# SCH_Basic_ESC_2023-04-21_EasyEDA.net
KiCad netlist of a schematic drawn in EasyEDA
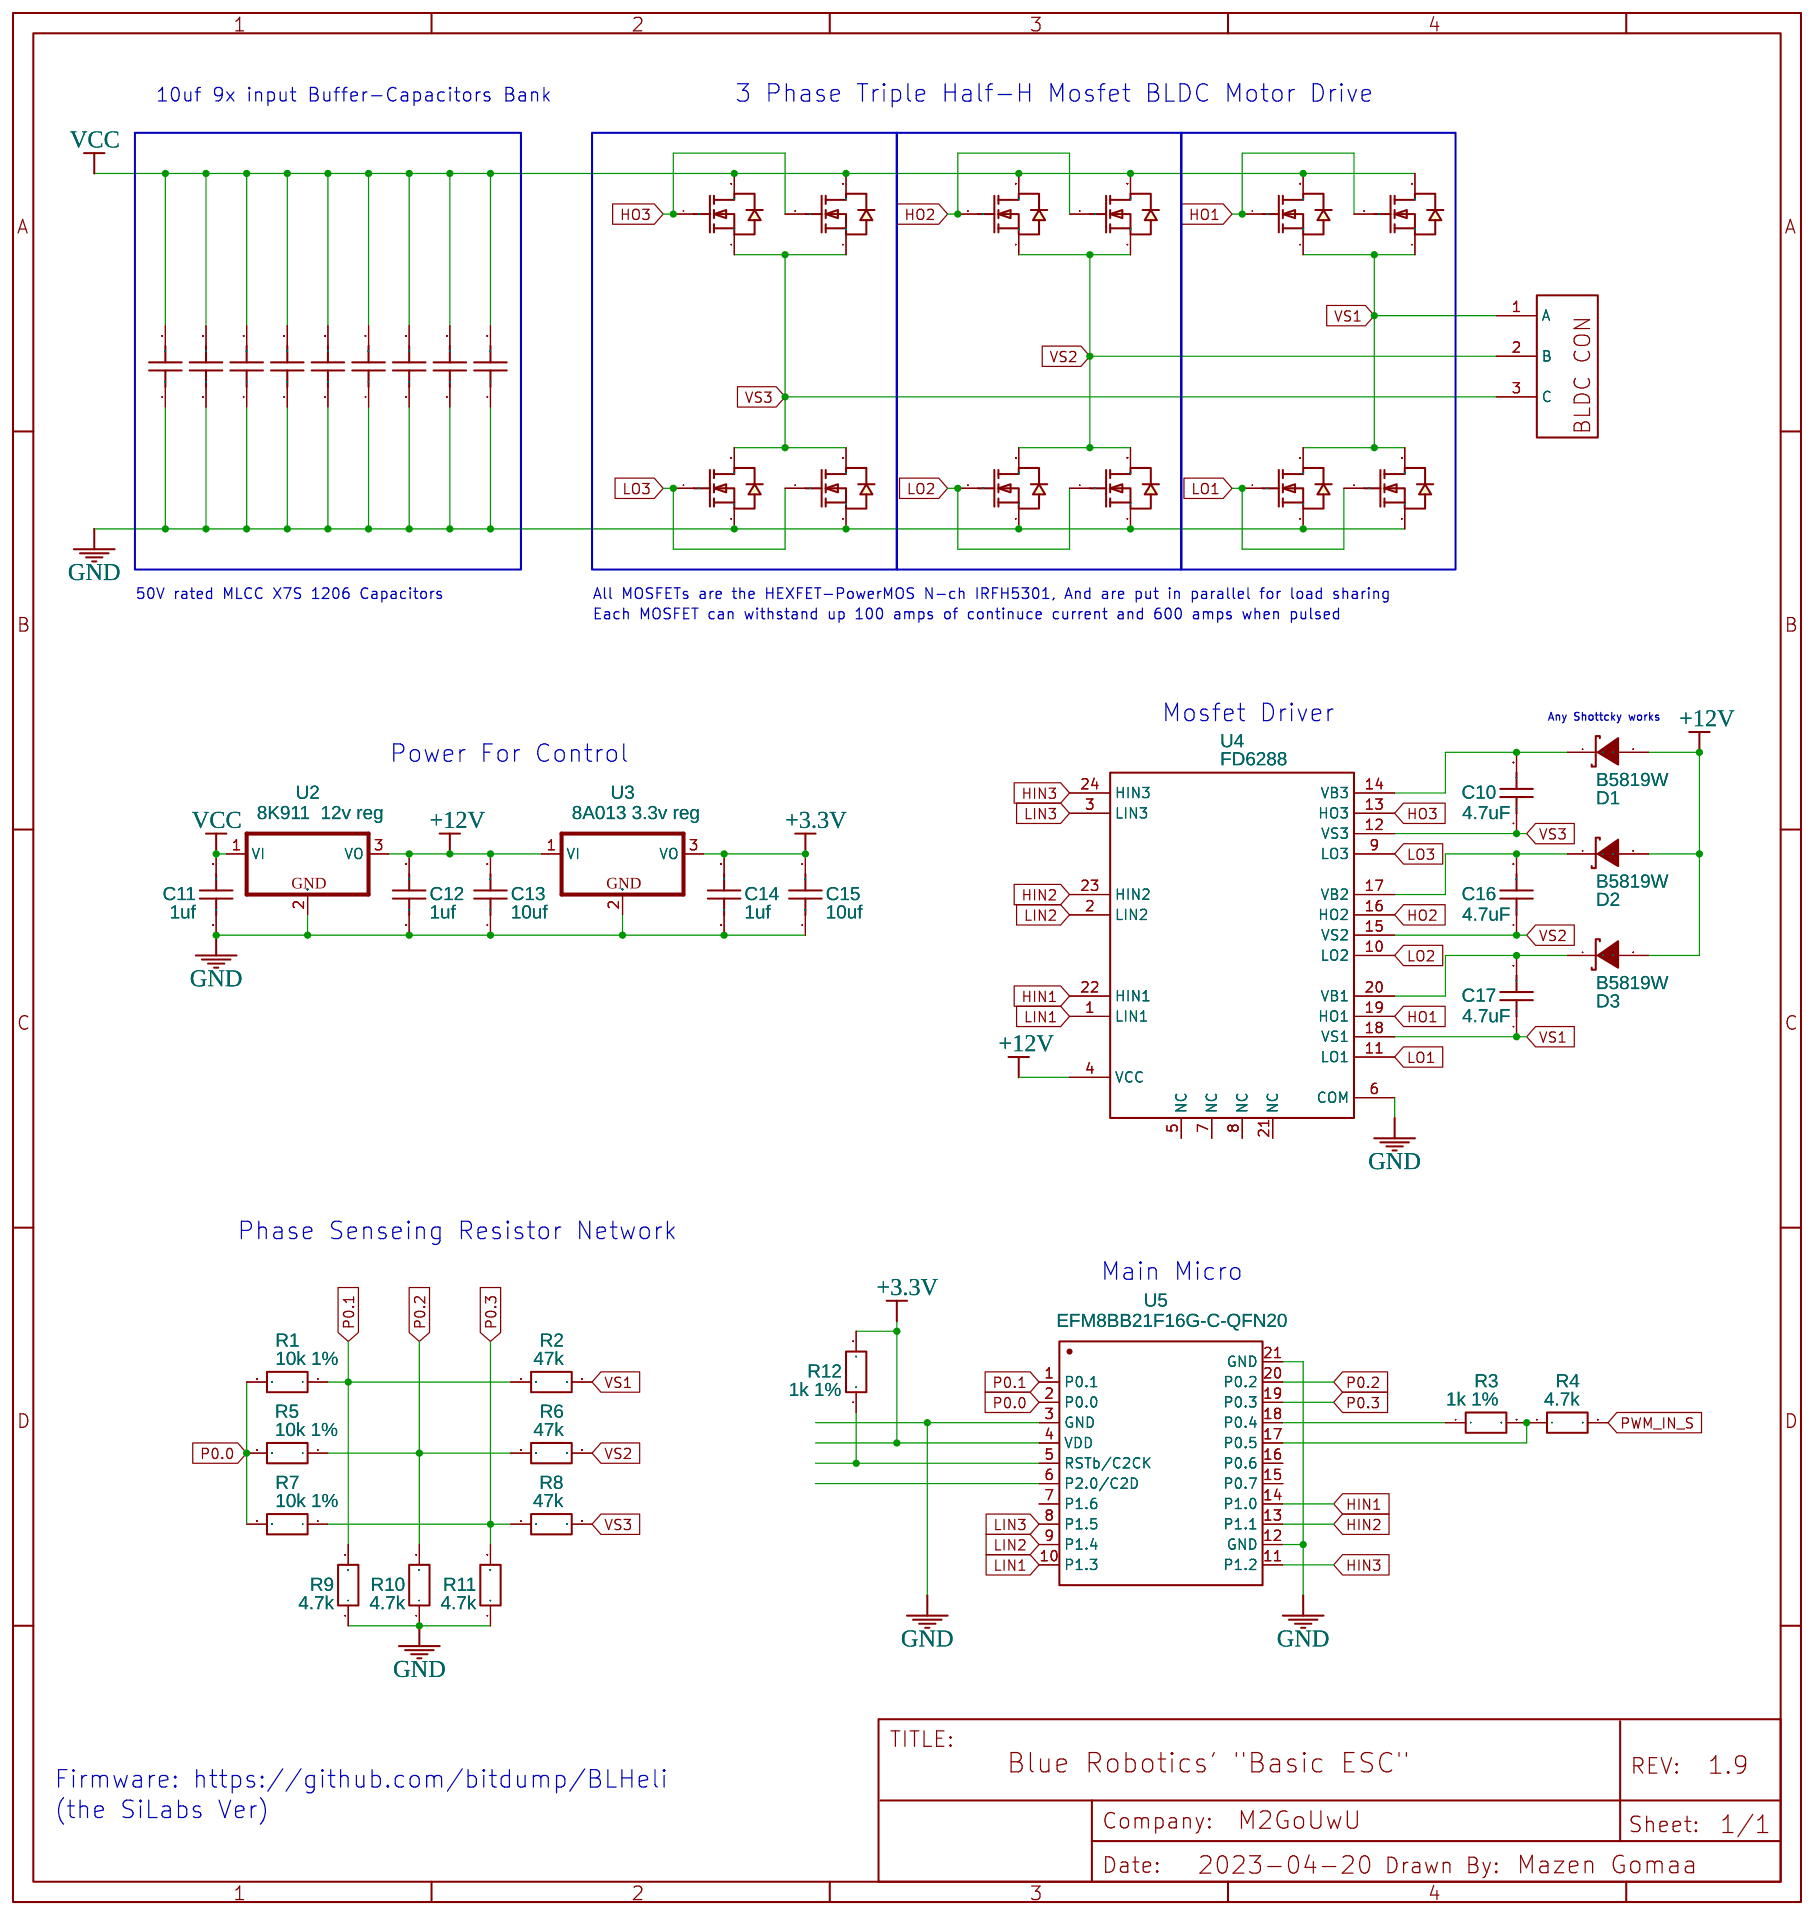
[diagram p0: schematic sheet]

(export (version "E")
  (design (tool "Eeschema 10.0.6"))
  (components
    (comp (ref "C1") (value "10uf") (libsource (lib "") (part "C_0603_US")))
    (comp (ref "C2") (value "10uf") (libsource (lib "") (part "C_0603_US")))
    (comp (ref "C3") (value "10uf") (libsource (lib "") (part "C_0603_US")))
    (comp (ref "C4") (value "10uf") (libsource (lib "") (part "C_0603_US")))
    (comp (ref "C5") (value "10uf") (libsource (lib "") (part "C_0603_US")))
    (comp (ref "C6") (value "10uf") (libsource (lib "") (part "C_0603_US")))
    (comp (ref "C7") (value "10uf") (libsource (lib "") (part "C_0603_US")))
    (comp (ref "C8") (value "10uf") (libsource (lib "") (part "C_0603_US")))
    (comp (ref "C9") (value "10uf") (libsource (lib "") (part "C_0603_US")))
    (comp (ref "C10")
      (value "4.7uF")
      (fields
        (field (name "BOM_Manufacturer Part") "TCC1206X5R475K160HT")
        (field (name "BOM_Supplier Part") "C380360")
      )
      (libsource (lib "") (part "TCC1206X5R475K160HT"))
    )
    (comp (ref "C11") (value "1uf") (libsource (lib "") (part "C_0603_US_1")))
    (comp (ref "C12") (value "1uf") (libsource (lib "") (part "C_0603_US")))
    (comp (ref "C13") (value "10uf") (libsource (lib "") (part "C_0603_US")))
    (comp (ref "C14") (value "1uf") (libsource (lib "") (part "C_0603_US")))
    (comp (ref "C15") (value "10uf") (libsource (lib "") (part "C_0603_US")))
    (comp (ref "C16")
      (value "4.7uF")
      (fields
        (field (name "BOM_Manufacturer Part") "TCC1206X5R475K160HT")
        (field (name "BOM_Supplier Part") "C380360")
      )
      (libsource (lib "") (part "TCC1206X5R475K160HT"))
    )
    (comp (ref "C17")
      (value "4.7uF")
      (fields
        (field (name "BOM_Manufacturer Part") "TCC1206X5R475K160HT")
        (field (name "BOM_Supplier Part") "C380360")
      )
      (libsource (lib "") (part "TCC1206X5R475K160HT"))
    )
    (comp (ref "D1")
      (value "B5819W")
      (fields (field (name "BOM_Supplier Part") "C64885"))
      (libsource (lib "") (part "B5819W"))
    )
    (comp (ref "D2")
      (value "B5819W")
      (fields (field (name "BOM_Supplier Part") "C64885"))
      (libsource (lib "") (part "B5819W"))
    )
    (comp (ref "D3")
      (value "B5819W")
      (fields (field (name "BOM_Supplier Part") "C64885"))
      (libsource (lib "") (part "B5819W"))
    )
    (comp (ref "Q1")
      (value "IRFH5301")
      (fields
        (field (name "BOM_Manufacturer Part") "IRFH5301PbF")
        (field (name "BOM_Supplier Part") "C82057")
      )
      (libsource (lib "") (part "IRFH5301"))
    )
    (comp (ref "Q2")
      (value "IRFH5301")
      (fields
        (field (name "BOM_Manufacturer Part") "IRFH5301PbF")
        (field (name "BOM_Supplier Part") "C82057")
      )
      (libsource (lib "") (part "IRFH5301"))
    )
    (comp (ref "Q3")
      (value "IRFH5301")
      (fields
        (field (name "BOM_Manufacturer Part") "IRFH5301PbF")
        (field (name "BOM_Supplier Part") "C82057")
      )
      (libsource (lib "") (part "IRFH5301"))
    )
    (comp (ref "Q4")
      (value "IRFH5301")
      (fields
        (field (name "BOM_Manufacturer Part") "IRFH5301PbF")
        (field (name "BOM_Supplier Part") "C82057")
      )
      (libsource (lib "") (part "IRFH5301"))
    )
    (comp (ref "Q5")
      (value "IRFH5301")
      (fields
        (field (name "BOM_Manufacturer Part") "IRFH5301PbF")
        (field (name "BOM_Supplier Part") "C82057")
      )
      (libsource (lib "") (part "IRFH5301"))
    )
    (comp (ref "Q6")
      (value "IRFH5301")
      (fields
        (field (name "BOM_Manufacturer Part") "IRFH5301PbF")
        (field (name "BOM_Supplier Part") "C82057")
      )
      (libsource (lib "") (part "IRFH5301"))
    )
    (comp (ref "Q7")
      (value "IRFH5301")
      (fields
        (field (name "BOM_Manufacturer Part") "IRFH5301PbF")
        (field (name "BOM_Supplier Part") "C82057")
      )
      (libsource (lib "") (part "IRFH5301"))
    )
    (comp (ref "Q8")
      (value "IRFH5301")
      (fields
        (field (name "BOM_Manufacturer Part") "IRFH5301PbF")
        (field (name "BOM_Supplier Part") "C82057")
      )
      (libsource (lib "") (part "IRFH5301"))
    )
    (comp (ref "Q9")
      (value "IRFH5301")
      (fields
        (field (name "BOM_Manufacturer Part") "IRFH5301PbF")
        (field (name "BOM_Supplier Part") "C82057")
      )
      (libsource (lib "") (part "IRFH5301"))
    )
    (comp (ref "Q10")
      (value "IRFH5301")
      (fields
        (field (name "BOM_Manufacturer Part") "IRFH5301PbF")
        (field (name "BOM_Supplier Part") "C82057")
      )
      (libsource (lib "") (part "IRFH5301"))
    )
    (comp (ref "Q11")
      (value "IRFH5301")
      (fields
        (field (name "BOM_Manufacturer Part") "IRFH5301PbF")
        (field (name "BOM_Supplier Part") "C82057")
      )
      (libsource (lib "") (part "IRFH5301"))
    )
    (comp (ref "Q12")
      (value "IRFH5301")
      (fields
        (field (name "BOM_Manufacturer Part") "IRFH5301PbF")
        (field (name "BOM_Supplier Part") "C82057")
      )
      (libsource (lib "") (part "IRFH5301"))
    )
    (comp (ref "R1") (value "10k 1%") (libsource (lib "") (part "R_0603_EU_2")))
    (comp (ref "R2") (value "47k") (libsource (lib "") (part "R_0603_EU_1")))
    (comp (ref "R3") (value "1k 1%") (libsource (lib "") (part "R_0603_EU_1")))
    (comp (ref "R4") (value "4.7k") (libsource (lib "") (part "R_0603_EU_1")))
    (comp (ref "R5") (value "10k 1%") (libsource (lib "") (part "R_0603_EU_2")))
    (comp (ref "R6") (value "47k") (libsource (lib "") (part "R_0603_EU_1")))
    (comp (ref "R7") (value "10k 1%") (libsource (lib "") (part "R_0603_EU_2")))
    (comp (ref "R8") (value "47k") (libsource (lib "") (part "R_0603_EU_1")))
    (comp (ref "R9") (value "4.7k") (libsource (lib "") (part "R_0603_EU")))
    (comp (ref "R10") (value "4.7k") (libsource (lib "") (part "R_0603_EU")))
    (comp (ref "R11") (value "4.7k") (libsource (lib "") (part "R_0603_EU")))
    (comp (ref "R12") (value "1k 1%") (libsource (lib "") (part "R_0603_EU")))
    (comp (ref "U1") (value "BLDC_CON") (libsource (lib "") (part "BLDC_CON")))
    (comp (ref "U2")
      (value "8K911  12v reg")
      (fields
        (field (name "BOM_Manufacturer Part") "K7805-2000L")
        (field (name "BOM_Supplier Part") "C96398")
      )
      (libsource (lib "") (part "K7805-2000L"))
    )
    (comp (ref "U3")
      (value "8A013 3.3v reg")
      (fields
        (field (name "BOM_Manufacturer Part") "K7805-2000L")
        (field (name "BOM_Supplier Part") "C96398")
      )
      (libsource (lib "") (part "K7805-2000L"))
    )
    (comp (ref "U4")
      (value "FD6288")
      (fields (field (name "BOM_Manufacturer Part") "FD6288T") (field (name "BOM_Supplier Part") "C97683"))
      (libsource (lib "") (part "FD6288"))
    )
    (comp (ref "U5")
      (value "EFM8BB21F16G-C-QFN20")
      (fields
        (field (name "BOM_Manufacturer Part") "EFM8BB21F16A-C-QFN20")
        (field (name "BOM_Supplier Part") "C430129")
      )
      (libsource (lib "") (part "EFM8BB21F16A-C-QFN20"))
    )
  )
  (nets
    (net (code "1") (name "+3.3V") (class "Default")
      (node (ref "C14") (pin "2") (pinfunction "2_2") (pintype "unspecified"))
      (node (ref "C15") (pin "2") (pinfunction "2_2") (pintype "unspecified"))
      (node (ref "R12") (pin "2") (pinfunction "2_2") (pintype "unspecified"))
      (node (ref "U3") (pin "3") (pinfunction "VO_3") (pintype "unspecified"))
      (node (ref "U5") (pin "4") (pinfunction "VDD_4") (pintype "unspecified"))
    )
    (net (code "2") (name "+12V") (class "Default")
      (node (ref "C12") (pin "2") (pinfunction "2_2") (pintype "unspecified"))
      (node (ref "C13") (pin "2") (pinfunction "2_2") (pintype "unspecified"))
      (node (ref "D1") (pin "2") (pinfunction "A_2") (pintype "unspecified"))
      (node (ref "D2") (pin "2") (pinfunction "A_2") (pintype "unspecified"))
      (node (ref "D3") (pin "2") (pinfunction "A_2") (pintype "unspecified"))
      (node (ref "U2") (pin "3") (pinfunction "VO_3") (pintype "unspecified"))
      (node (ref "U3") (pin "1") (pinfunction "VI_1") (pintype "input"))
      (node (ref "U4") (pin "4") (pinfunction "VCC_4") (pintype "unspecified"))
    )
    (net (code "3") (name "GND") (class "Default")
      (node (ref "C1") (pin "1") (pinfunction "1_1") (pintype "unspecified"))
      (node (ref "C11") (pin "1") (pinfunction "1_1") (pintype "unspecified"))
      (node (ref "C12") (pin "1") (pinfunction "1_1") (pintype "unspecified"))
      (node (ref "C13") (pin "1") (pinfunction "1_1") (pintype "unspecified"))
      (node (ref "C14") (pin "1") (pinfunction "1_1") (pintype "unspecified"))
      (node (ref "C15") (pin "1") (pinfunction "1_1") (pintype "unspecified"))
      (node (ref "C2") (pin "1") (pinfunction "1_1") (pintype "unspecified"))
      (node (ref "C3") (pin "1") (pinfunction "1_1") (pintype "unspecified"))
      (node (ref "C4") (pin "1") (pinfunction "1_1") (pintype "unspecified"))
      (node (ref "C5") (pin "1") (pinfunction "1_1") (pintype "unspecified"))
      (node (ref "C6") (pin "1") (pinfunction "1_1") (pintype "unspecified"))
      (node (ref "C7") (pin "1") (pinfunction "1_1") (pintype "unspecified"))
      (node (ref "C8") (pin "1") (pinfunction "1_1") (pintype "unspecified"))
      (node (ref "C9") (pin "1") (pinfunction "1_1") (pintype "unspecified"))
      (node (ref "Q10") (pin "1") (pinfunction "S_1") (pintype "unspecified"))
      (node (ref "Q11") (pin "1") (pinfunction "S_1") (pintype "unspecified"))
      (node (ref "Q12") (pin "1") (pinfunction "S_1") (pintype "unspecified"))
      (node (ref "Q7") (pin "1") (pinfunction "S_1") (pintype "unspecified"))
      (node (ref "Q8") (pin "1") (pinfunction "S_1") (pintype "unspecified"))
      (node (ref "Q9") (pin "1") (pinfunction "S_1") (pintype "unspecified"))
      (node (ref "R10") (pin "1") (pinfunction "1_1") (pintype "unspecified"))
      (node (ref "R11") (pin "1") (pinfunction "1_1") (pintype "unspecified"))
      (node (ref "R9") (pin "1") (pinfunction "1_1") (pintype "unspecified"))
      (node (ref "U2") (pin "2") (pinfunction "GND_2") (pintype "unspecified"))
      (node (ref "U3") (pin "2") (pinfunction "GND_2") (pintype "unspecified"))
      (node (ref "U4") (pin "6") (pinfunction "COM_6") (pintype "unspecified"))
      (node (ref "U5") (pin "12") (pinfunction "GND_12") (pintype "unspecified"))
      (node (ref "U5") (pin "21") (pinfunction "GND_21") (pintype "unspecified"))
      (node (ref "U5") (pin "3") (pinfunction "GND_3") (pintype "unspecified"))
    )
    (net (code "4") (name "HIN1") (class "Default")
      (node (ref "U4") (pin "22") (pinfunction "HIN1_22") (pintype "unspecified"))
      (node (ref "U5") (pin "14") (pinfunction "P1.0_14") (pintype "unspecified"))
    )
    (net (code "5") (name "HIN2") (class "Default")
      (node (ref "U4") (pin "23") (pinfunction "HIN2_23") (pintype "unspecified"))
      (node (ref "U5") (pin "13") (pinfunction "P1.1_13") (pintype "unspecified"))
    )
    (net (code "6") (name "HIN3") (class "Default")
      (node (ref "U4") (pin "24") (pinfunction "HIN3_24") (pintype "unspecified"))
      (node (ref "U5") (pin "11") (pinfunction "P1.2_11") (pintype "unspecified"))
    )
    (net (code "7") (name "HO1") (class "Default")
      (node (ref "Q5") (pin "4") (pinfunction "G_4") (pintype "unspecified"))
      (node (ref "Q6") (pin "4") (pinfunction "G_4") (pintype "unspecified"))
      (node (ref "U4") (pin "19") (pinfunction "HO1_19") (pintype "unspecified"))
    )
    (net (code "8") (name "HO2") (class "Default")
      (node (ref "Q3") (pin "4") (pinfunction "G_4") (pintype "unspecified"))
      (node (ref "Q4") (pin "4") (pinfunction "G_4") (pintype "unspecified"))
      (node (ref "U4") (pin "16") (pinfunction "HO2_16") (pintype "unspecified"))
    )
    (net (code "9") (name "HO3") (class "Default")
      (node (ref "Q1") (pin "4") (pinfunction "G_4") (pintype "unspecified"))
      (node (ref "Q2") (pin "4") (pinfunction "G_4") (pintype "unspecified"))
      (node (ref "U4") (pin "13") (pinfunction "HO3_13") (pintype "unspecified"))
    )
    (net (code "10") (name "LIN1") (class "Default")
      (node (ref "U4") (pin "1") (pinfunction "LIN1_1") (pintype "unspecified"))
      (node (ref "U5") (pin "10") (pinfunction "P1.3_10") (pintype "unspecified"))
    )
    (net (code "11") (name "LIN2") (class "Default")
      (node (ref "U4") (pin "2") (pinfunction "LIN2_2") (pintype "unspecified"))
      (node (ref "U5") (pin "9") (pinfunction "P1.4_9") (pintype "unspecified"))
    )
    (net (code "12") (name "LIN3") (class "Default")
      (node (ref "U4") (pin "3") (pinfunction "LIN3_3") (pintype "unspecified"))
      (node (ref "U5") (pin "8") (pinfunction "P1.5_8") (pintype "unspecified"))
    )
    (net (code "13") (name "LO1") (class "Default")
      (node (ref "Q11") (pin "4") (pinfunction "G_4") (pintype "unspecified"))
      (node (ref "Q12") (pin "4") (pinfunction "G_4") (pintype "unspecified"))
      (node (ref "U4") (pin "11") (pinfunction "LO1_11") (pintype "unspecified"))
    )
    (net (code "14") (name "LO2") (class "Default")
      (node (ref "Q10") (pin "4") (pinfunction "G_4") (pintype "unspecified"))
      (node (ref "Q9") (pin "4") (pinfunction "G_4") (pintype "unspecified"))
      (node (ref "U4") (pin "10") (pinfunction "LO2_10") (pintype "unspecified"))
    )
    (net (code "15") (name "LO3") (class "Default")
      (node (ref "Q7") (pin "4") (pinfunction "G_4") (pintype "unspecified"))
      (node (ref "Q8") (pin "4") (pinfunction "G_4") (pintype "unspecified"))
      (node (ref "U4") (pin "9") (pinfunction "LO3_9") (pintype "unspecified"))
    )
    (net (code "16") (name "Net-(D1-K)") (class "Default")
      (node (ref "C10") (pin "2") (pinfunction "2_2") (pintype "unspecified"))
      (node (ref "D1") (pin "1") (pinfunction "K_1") (pintype "unspecified"))
      (node (ref "U4") (pin "14") (pinfunction "VB3_14") (pintype "unspecified"))
    )
    (net (code "17") (name "Net-(D2-K)") (class "Default")
      (node (ref "C16") (pin "2") (pinfunction "2_2") (pintype "unspecified"))
      (node (ref "D2") (pin "1") (pinfunction "K_1") (pintype "unspecified"))
      (node (ref "U4") (pin "17") (pinfunction "VB2_17") (pintype "unspecified"))
    )
    (net (code "18") (name "Net-(D3-K)") (class "Default")
      (node (ref "C17") (pin "2") (pinfunction "2_2") (pintype "unspecified"))
      (node (ref "D3") (pin "1") (pinfunction "K_1") (pintype "unspecified"))
      (node (ref "U4") (pin "20") (pinfunction "VB1_20") (pintype "unspecified"))
    )
    (net (code "19") (name "Net-(U5-P0.4)") (class "Default")
      (node (ref "R3") (pin "1") (pinfunction "1_1") (pintype "unspecified"))
      (node (ref "U5") (pin "18") (pinfunction "P0.4_18") (pintype "unspecified"))
    )
    (net (code "20") (name "Net-(U5-P0.5)") (class "Default")
      (node (ref "R3") (pin "2") (pinfunction "2_2") (pintype "unspecified"))
      (node (ref "R4") (pin "1") (pinfunction "1_1") (pintype "unspecified"))
      (node (ref "U5") (pin "17") (pinfunction "P0.5_17") (pintype "unspecified"))
    )
    (net (code "21") (name "Net-(U5-RSTb{slash}C2CK)") (class "Default")
      (node (ref "R12") (pin "1") (pinfunction "1_1") (pintype "unspecified"))
      (node (ref "U5") (pin "5") (pinfunction "RSTb/C2CK_5") (pintype "unspecified"))
    )
    (net (code "22") (name "P0.0") (class "Default")
      (node (ref "R1") (pin "2") (pinfunction "2_2") (pintype "unspecified"))
      (node (ref "R5") (pin "2") (pinfunction "2_2") (pintype "unspecified"))
      (node (ref "R7") (pin "2") (pinfunction "2_2") (pintype "unspecified"))
      (node (ref "U5") (pin "2") (pinfunction "P0.0_2") (pintype "unspecified"))
    )
    (net (code "23") (name "P0.1") (class "Default")
      (node (ref "R1") (pin "1") (pinfunction "1_1") (pintype "unspecified"))
      (node (ref "R2") (pin "1") (pinfunction "1_1") (pintype "unspecified"))
      (node (ref "R9") (pin "2") (pinfunction "2_2") (pintype "unspecified"))
      (node (ref "U5") (pin "1") (pinfunction "P0.1_1") (pintype "unspecified"))
    )
    (net (code "24") (name "P0.2") (class "Default")
      (node (ref "R10") (pin "2") (pinfunction "2_2") (pintype "unspecified"))
      (node (ref "R5") (pin "1") (pinfunction "1_1") (pintype "unspecified"))
      (node (ref "R6") (pin "1") (pinfunction "1_1") (pintype "unspecified"))
      (node (ref "U5") (pin "20") (pinfunction "P0.2_20") (pintype "unspecified"))
    )
    (net (code "25") (name "P0.3") (class "Default")
      (node (ref "R11") (pin "2") (pinfunction "2_2") (pintype "unspecified"))
      (node (ref "R7") (pin "1") (pinfunction "1_1") (pintype "unspecified"))
      (node (ref "R8") (pin "1") (pinfunction "1_1") (pintype "unspecified"))
      (node (ref "U5") (pin "19") (pinfunction "P0.3_19") (pintype "unspecified"))
    )
    (net (code "26") (name "PWM_IN_S") (class "Default")
      (node (ref "R4") (pin "2") (pinfunction "2_2") (pintype "unspecified"))
    )
    (net (code "27") (name "VCC") (class "Default")
      (node (ref "C1") (pin "2") (pinfunction "2_2") (pintype "unspecified"))
      (node (ref "C11") (pin "2") (pinfunction "2_2") (pintype "unspecified"))
      (node (ref "C2") (pin "2") (pinfunction "2_2") (pintype "unspecified"))
      (node (ref "C3") (pin "2") (pinfunction "2_2") (pintype "unspecified"))
      (node (ref "C4") (pin "2") (pinfunction "2_2") (pintype "unspecified"))
      (node (ref "C5") (pin "2") (pinfunction "2_2") (pintype "unspecified"))
      (node (ref "C6") (pin "2") (pinfunction "2_2") (pintype "unspecified"))
      (node (ref "C7") (pin "2") (pinfunction "2_2") (pintype "unspecified"))
      (node (ref "C8") (pin "2") (pinfunction "2_2") (pintype "unspecified"))
      (node (ref "C9") (pin "2") (pinfunction "2_2") (pintype "unspecified"))
      (node (ref "Q1") (pin "5") (pinfunction "D_5") (pintype "unspecified"))
      (node (ref "Q2") (pin "5") (pinfunction "D_5") (pintype "unspecified"))
      (node (ref "Q3") (pin "5") (pinfunction "D_5") (pintype "unspecified"))
      (node (ref "Q4") (pin "5") (pinfunction "D_5") (pintype "unspecified"))
      (node (ref "Q5") (pin "5") (pinfunction "D_5") (pintype "unspecified"))
      (node (ref "Q6") (pin "5") (pinfunction "D_5") (pintype "unspecified"))
      (node (ref "U2") (pin "1") (pinfunction "VI_1") (pintype "input"))
    )
    (net (code "28") (name "VS1") (class "Default")
      (node (ref "C17") (pin "1") (pinfunction "1_1") (pintype "unspecified"))
      (node (ref "Q11") (pin "5") (pinfunction "D_5") (pintype "unspecified"))
      (node (ref "Q12") (pin "5") (pinfunction "D_5") (pintype "unspecified"))
      (node (ref "Q5") (pin "1") (pinfunction "S_1") (pintype "unspecified"))
      (node (ref "Q6") (pin "1") (pinfunction "S_1") (pintype "unspecified"))
      (node (ref "R2") (pin "2") (pinfunction "2_2") (pintype "unspecified"))
      (node (ref "U1") (pin "1") (pinfunction "A_1") (pintype "unspecified"))
      (node (ref "U4") (pin "18") (pinfunction "VS1_18") (pintype "unspecified"))
    )
    (net (code "29") (name "VS2") (class "Default")
      (node (ref "C16") (pin "1") (pinfunction "1_1") (pintype "unspecified"))
      (node (ref "Q10") (pin "5") (pinfunction "D_5") (pintype "unspecified"))
      (node (ref "Q3") (pin "1") (pinfunction "S_1") (pintype "unspecified"))
      (node (ref "Q4") (pin "1") (pinfunction "S_1") (pintype "unspecified"))
      (node (ref "Q9") (pin "5") (pinfunction "D_5") (pintype "unspecified"))
      (node (ref "R6") (pin "2") (pinfunction "2_2") (pintype "unspecified"))
      (node (ref "U1") (pin "2") (pinfunction "B_2") (pintype "unspecified"))
      (node (ref "U4") (pin "15") (pinfunction "VS2_15") (pintype "unspecified"))
    )
    (net (code "30") (name "VS3") (class "Default")
      (node (ref "C10") (pin "1") (pinfunction "1_1") (pintype "unspecified"))
      (node (ref "Q1") (pin "1") (pinfunction "S_1") (pintype "unspecified"))
      (node (ref "Q2") (pin "1") (pinfunction "S_1") (pintype "unspecified"))
      (node (ref "Q7") (pin "5") (pinfunction "D_5") (pintype "unspecified"))
      (node (ref "Q8") (pin "5") (pinfunction "D_5") (pintype "unspecified"))
      (node (ref "R8") (pin "2") (pinfunction "2_2") (pintype "unspecified"))
      (node (ref "U1") (pin "3") (pinfunction "C_3") (pintype "unspecified"))
      (node (ref "U4") (pin "12") (pinfunction "VS3_12") (pintype "unspecified"))
    )
    (net (code "31") (name "unconnected-(U4-NC-Pad5)") (class "Default")
      (node (ref "U4") (pin "5") (pinfunction "NC_5") (pintype "unspecified"))
    )
    (net (code "32") (name "unconnected-(U4-NC-Pad7)") (class "Default")
      (node (ref "U4") (pin "7") (pinfunction "NC_7") (pintype "unspecified"))
    )
    (net (code "33") (name "unconnected-(U4-NC-Pad8)") (class "Default")
      (node (ref "U4") (pin "8") (pinfunction "NC_8") (pintype "unspecified"))
    )
    (net (code "34") (name "unconnected-(U4-NC-Pad21)") (class "Default")
      (node (ref "U4") (pin "21") (pinfunction "NC_21") (pintype "unspecified"))
    )
    (net (code "35") (name "unconnected-(U5-P0.6-Pad16)") (class "Default")
      (node (ref "U5") (pin "16") (pinfunction "P0.6_16") (pintype "unspecified"))
    )
    (net (code "36") (name "unconnected-(U5-P0.7-Pad15)") (class "Default")
      (node (ref "U5") (pin "15") (pinfunction "P0.7_15") (pintype "unspecified"))
    )
    (net (code "37") (name "unconnected-(U5-P1.6-Pad7)") (class "Default")
      (node (ref "U5") (pin "7") (pinfunction "P1.6_7") (pintype "unspecified"))
    )
    (net (code "38") (name "unconnected-(U5-P2.0{slash}C2D-Pad6)") (class "Default")
      (node (ref "U5") (pin "6") (pinfunction "P2.0/C2D_6") (pintype "unspecified"))
    )
  )
)
